# Stick_IMUinator2368.net
KiCad netlist of a schematic drawn in EAGLE
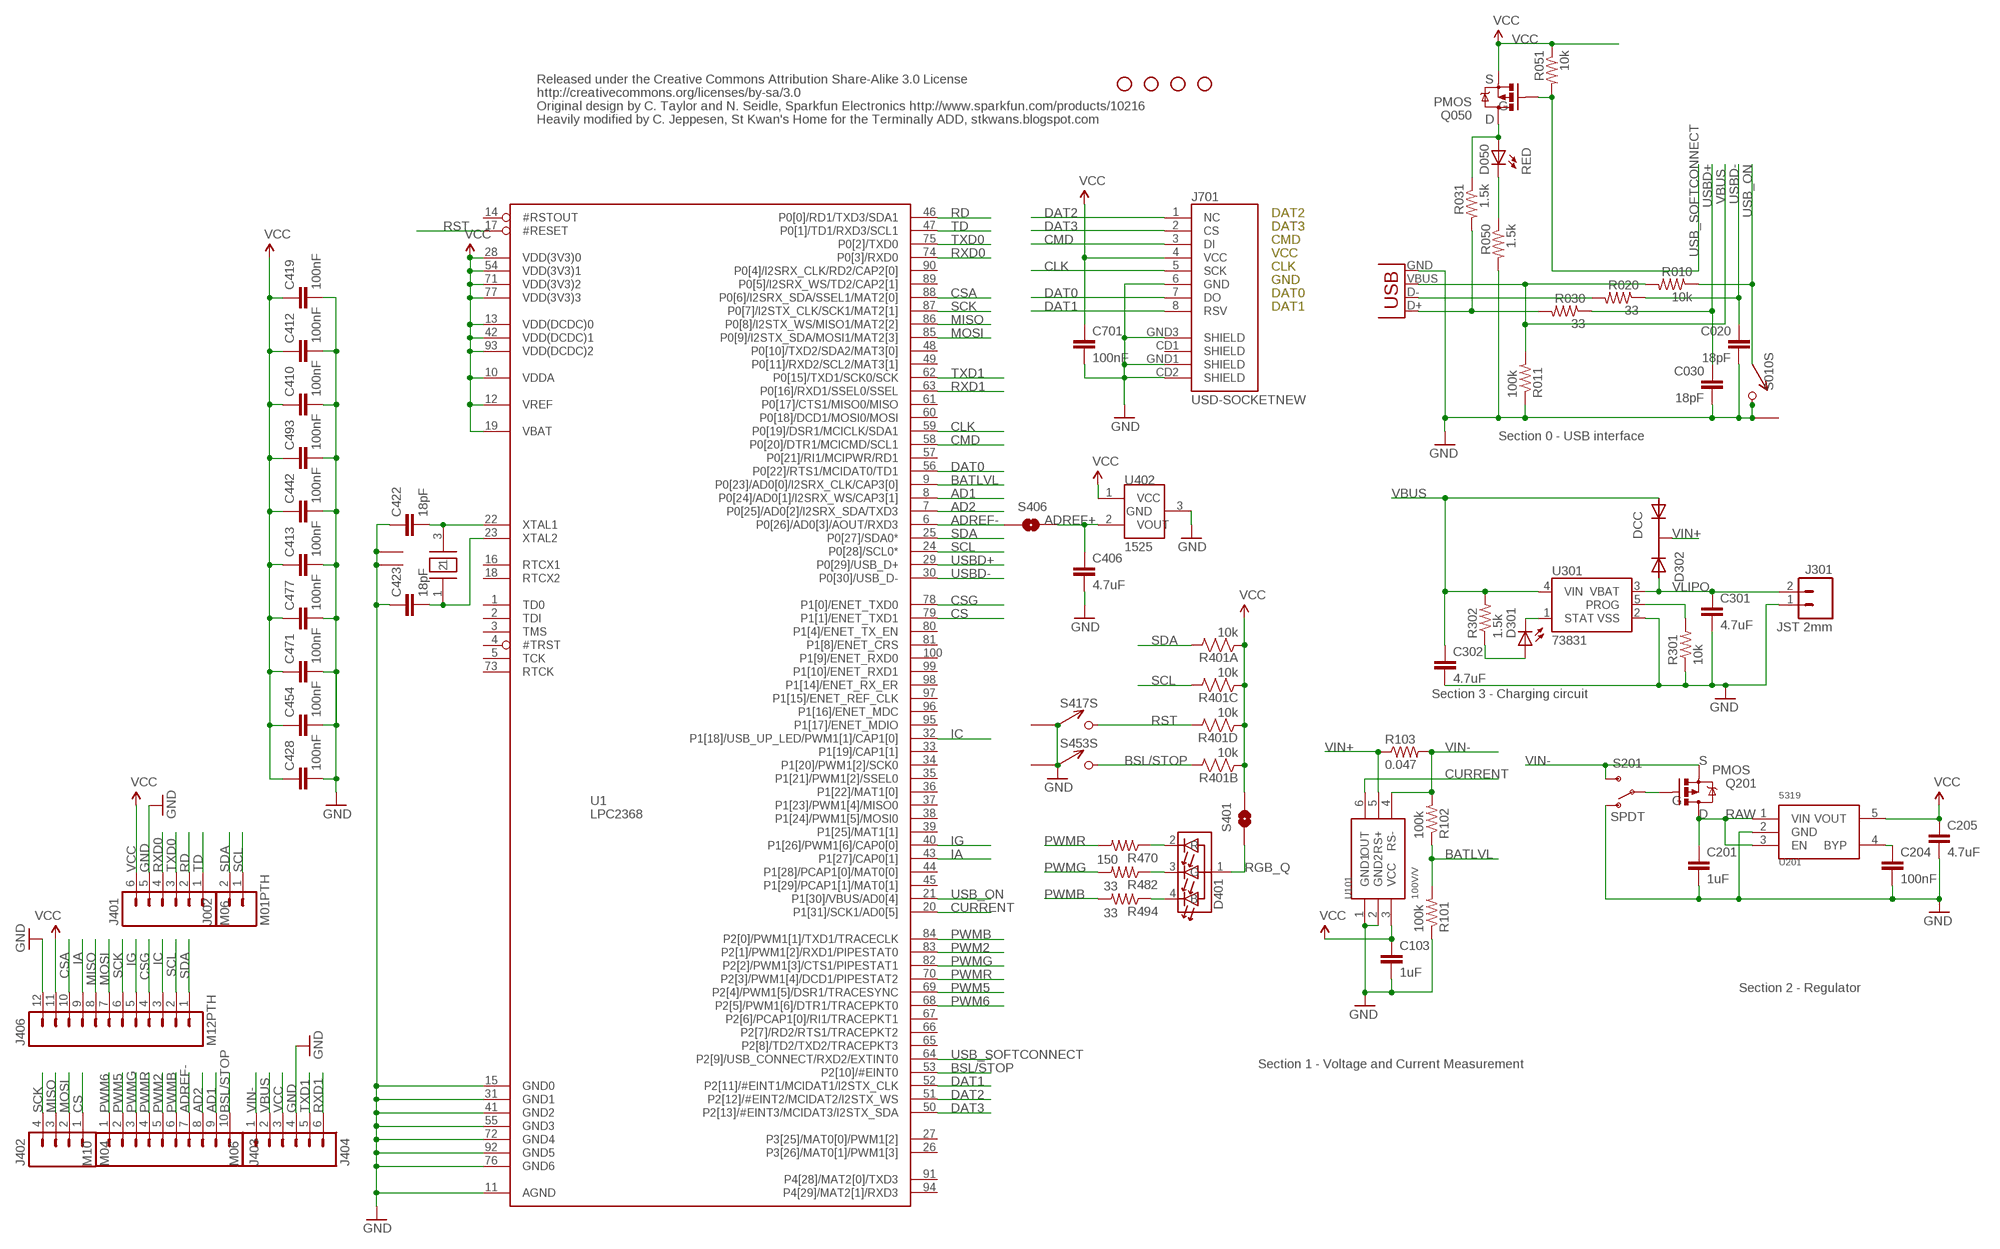
[diagram p0: schematic, sheet 1]

(export (version "E")
  (design (tool "Eeschema 10.0.6"))
  (components
    (comp (ref "C020")
      (value "18pF")
      (footprint "eagle-import:0402-CAP")
      (libsource (lib "eagle-import") (part "CAP0402-CAP"))
    )
    (comp (ref "C030")
      (value "18pF")
      (footprint "eagle-import:0402-CAP")
      (libsource (lib "eagle-import") (part "CAP0402-CAP"))
    )
    (comp (ref "C103")
      (value "1uF")
      (footprint "eagle-import:0402-CAP")
      (libsource (lib "eagle-import") (part "CAP0402-CAP"))
    )
    (comp (ref "C201")
      (value "1uF")
      (footprint "eagle-import:0402-CAP")
      (libsource (lib "eagle-import") (part "CAP0402-CAP"))
    )
    (comp (ref "C204")
      (value "100nF")
      (footprint "eagle-import:0402-CAP")
      (libsource (lib "eagle-import") (part "CAP0402-CAP"))
    )
    (comp (ref "C205")
      (value "4.7uF")
      (footprint "eagle-import:0402-CAP")
      (libsource (lib "eagle-import") (part "CAP0402-CAP"))
    )
    (comp (ref "C301")
      (value "4.7uF")
      (footprint "eagle-import:0402-CAP")
      (libsource (lib "eagle-import") (part "CAP0402-CAP"))
    )
    (comp (ref "C302")
      (value "4.7uF")
      (footprint "eagle-import:0402-CAP")
      (libsource (lib "eagle-import") (part "CAP0402-CAP"))
    )
    (comp (ref "C406")
      (value "4.7uF")
      (footprint "eagle-import:0402-CAP")
      (libsource (lib "eagle-import") (part "CAP0402-CAP"))
    )
    (comp (ref "C410")
      (value "100nF")
      (footprint "eagle-import:0402-CAP")
      (libsource (lib "eagle-import") (part "CAP0402-CAP"))
    )
    (comp (ref "C412")
      (value "100nF")
      (footprint "eagle-import:0402-CAP")
      (libsource (lib "eagle-import") (part "CAP0402-CAP"))
    )
    (comp (ref "C413")
      (value "100nF")
      (footprint "eagle-import:0402-CAP")
      (libsource (lib "eagle-import") (part "CAP0402-CAP"))
    )
    (comp (ref "C419")
      (value "100nF")
      (footprint "eagle-import:0402-CAP")
      (libsource (lib "eagle-import") (part "CAP0402-CAP"))
    )
    (comp (ref "C422")
      (value "18pF")
      (footprint "eagle-import:0402-CAP")
      (libsource (lib "eagle-import") (part "CAP0402-CAP"))
    )
    (comp (ref "C423")
      (value "18pF")
      (footprint "eagle-import:0402-CAP")
      (libsource (lib "eagle-import") (part "CAP0402-CAP"))
    )
    (comp (ref "C428")
      (value "100nF")
      (footprint "eagle-import:0402-CAP")
      (libsource (lib "eagle-import") (part "CAP0402-CAP"))
    )
    (comp (ref "C442")
      (value "100nF")
      (footprint "eagle-import:0402-CAP")
      (libsource (lib "eagle-import") (part "CAP0402-CAP"))
    )
    (comp (ref "C454")
      (value "100nF")
      (footprint "eagle-import:0402-CAP")
      (libsource (lib "eagle-import") (part "CAP0402-CAP"))
    )
    (comp (ref "C471")
      (value "100nF")
      (footprint "eagle-import:0402-CAP")
      (libsource (lib "eagle-import") (part "CAP0402-CAP"))
    )
    (comp (ref "C477")
      (value "100nF")
      (footprint "eagle-import:0402-CAP")
      (libsource (lib "eagle-import") (part "CAP0402-CAP"))
    )
    (comp (ref "C493")
      (value "100nF")
      (footprint "eagle-import:0402-CAP")
      (libsource (lib "eagle-import") (part "CAP0402-CAP"))
    )
    (comp (ref "C701")
      (value "100nF")
      (footprint "eagle-import:0402-CAP")
      (libsource (lib "eagle-import") (part "CAP0402-CAP"))
    )
    (comp (ref "D050")
      (value "RED")
      (footprint "eagle-import:LED-0603")
      (libsource (lib "eagle-import") (part "LED0603"))
    )
    (comp (ref "D301")
      (value "RED")
      (footprint "eagle-import:LED-0603")
      (libsource (lib "eagle-import") (part "LED0603"))
    )
    (comp (ref "D302")
      (value "DCC")
      (footprint "eagle-import:SOT-23-3")
      (libsource (lib "eagle-import") (part "PMEG2005CT"))
    )
    (comp (ref "D401")
      (value "RGB")
      (footprint "eagle-import:HSMF-C118")
      (libsource (lib "eagle-import") (part "HSMF-C118"))
    )
    (comp (ref "J001")
      (value "USBSMD")
      (footprint "eagle-import:USB-MINIB")
      (libsource (lib "eagle-import") (part "USBSMD"))
    )
    (comp (ref "J002")
      (value "M01PTH")
      (footprint "eagle-import:1X02")
      (libsource (lib "eagle-import") (part "M02PTH"))
    )
    (comp (ref "J301")
      (value "JST 2mm")
      (footprint "eagle-import:JST-2-SMD")
      (libsource (lib "eagle-import") (part "M02-JST-2MM-SMT"))
    )
    (comp (ref "J401")
      (value "M06")
      (footprint "eagle-import:1X06")
      (libsource (lib "eagle-import") (part "M06SIP"))
    )
    (comp (ref "J402")
      (value "M04")
      (footprint "eagle-import:1X04")
      (libsource (lib "eagle-import") (part "M04PTH"))
    )
    (comp (ref "J403")
      (value "M10")
      (footprint "eagle-import:1X10")
      (libsource (lib "eagle-import") (part "M10{dblquote}"))
    )
    (comp (ref "J404")
      (value "M06")
      (footprint "eagle-import:1X06")
      (libsource (lib "eagle-import") (part "M06SIP"))
    )
    (comp (ref "J406")
      (value "M12PTH")
      (footprint "eagle-import:1X12")
      (libsource (lib "eagle-import") (part "M12PTH"))
    )
    (comp (ref "J701")
      (value "USD-SOCKETNEW")
      (footprint "eagle-import:MICRO-SD-SOCKET-PP")
      (libsource (lib "eagle-import") (part "USD-SOCKETNEW"))
    )
    (comp (ref "JP1")
      (value "STAND-OFF")
      (footprint "eagle-import:STAND-OFF")
      (libsource (lib "eagle-import") (part "STAND-OFF"))
    )
    (comp (ref "JP2")
      (value "STAND-OFF")
      (footprint "eagle-import:STAND-OFF")
      (libsource (lib "eagle-import") (part "STAND-OFF"))
    )
    (comp (ref "JP3")
      (value "STAND-OFF")
      (footprint "eagle-import:STAND-OFF")
      (libsource (lib "eagle-import") (part "STAND-OFF"))
    )
    (comp (ref "JP4")
      (value "STAND-OFF")
      (footprint "eagle-import:STAND-OFF")
      (libsource (lib "eagle-import") (part "STAND-OFF"))
    )
    (comp (ref "Q050")
      (value "PMOS")
      (footprint "eagle-import:SOT23-3")
      (libsource (lib "eagle-import") (part "MOSFET-PCHANNELSMD"))
    )
    (comp (ref "Q201")
      (value "PMOS")
      (footprint "eagle-import:SOT23-3")
      (libsource (lib "eagle-import") (part "MOSFET-PCHANNELSMD"))
    )
    (comp (ref "R010")
      (value "10k")
      (footprint "eagle-import:0402-RES")
      (libsource (lib "eagle-import") (part "RESISTOR0402-RES"))
    )
    (comp (ref "R011")
      (value "100k")
      (footprint "eagle-import:0402-RES")
      (libsource (lib "eagle-import") (part "RESISTOR0402-RES"))
    )
    (comp (ref "R020")
      (value "33")
      (footprint "eagle-import:0402-RES")
      (libsource (lib "eagle-import") (part "RESISTOR0402-RES"))
    )
    (comp (ref "R030")
      (value "33")
      (footprint "eagle-import:0402-RES")
      (libsource (lib "eagle-import") (part "RESISTOR0402-RES"))
    )
    (comp (ref "R031")
      (value "1.5k")
      (footprint "eagle-import:0402-RES")
      (libsource (lib "eagle-import") (part "RESISTOR0402-RES"))
    )
    (comp (ref "R050")
      (value "1.5k")
      (footprint "eagle-import:0402-RES")
      (libsource (lib "eagle-import") (part "RESISTOR0402-RES"))
    )
    (comp (ref "R051")
      (value "10k")
      (footprint "eagle-import:0402-RES")
      (libsource (lib "eagle-import") (part "RESISTOR0402-RES"))
    )
    (comp (ref "R101")
      (value "100k")
      (footprint "eagle-import:0402-RES")
      (libsource (lib "eagle-import") (part "RESISTOR0402-RES"))
    )
    (comp (ref "R102")
      (value "100k")
      (footprint "eagle-import:0402-RES")
      (libsource (lib "eagle-import") (part "RESISTOR0402-RES"))
    )
    (comp (ref "R103")
      (value "0.047")
      (footprint "eagle-import:0402-RES")
      (libsource (lib "eagle-import") (part "RESISTOR0402-RES"))
    )
    (comp (ref "R301")
      (value "10k")
      (footprint "eagle-import:0402-RES")
      (libsource (lib "eagle-import") (part "RESISTOR0402-RES"))
    )
    (comp (ref "R302")
      (value "1.5k")
      (footprint "eagle-import:0402-RES")
      (libsource (lib "eagle-import") (part "RESISTOR0402-RES"))
    )
    (comp (ref "R401")
      (value "10k")
      (footprint "eagle-import:CRA04")
      (libsource (lib "eagle-import") (part "RP404"))
    )
    (comp (ref "R470")
      (value "150")
      (footprint "eagle-import:0402-RES")
      (libsource (lib "eagle-import") (part "RESISTOR0402-RES"))
    )
    (comp (ref "R482")
      (value "33")
      (footprint "eagle-import:0402-RES")
      (libsource (lib "eagle-import") (part "RESISTOR0402-RES"))
    )
    (comp (ref "R494")
      (value "33")
      (footprint "eagle-import:0402-RES")
      (libsource (lib "eagle-import") (part "RESISTOR0402-RES"))
    )
    (comp (ref "S010")
      (value "SPST")
      (footprint "eagle-import:B3U-1100P")
      (libsource (lib "eagle-import") (part "B3U-1100P"))
    )
    (comp (ref "S201")
      (value "SPDT")
      (footprint "eagle-import:AYZ0202")
      (libsource (lib "eagle-import") (part "SWITCH-SPSTSMD"))
    )
    (comp (ref "S401")
      (value "SOLDERJUMPERNO")
      (footprint "eagle-import:SJ_2S-NO")
      (libsource (lib "eagle-import") (part "SOLDERJUMPERNO"))
    )
    (comp (ref "S406")
      (value "SOLDERJUMPERNO")
      (footprint "eagle-import:SJ_2S-NO")
      (libsource (lib "eagle-import") (part "SOLDERJUMPERNO"))
    )
    (comp (ref "S417")
      (value "SPST")
      (footprint "eagle-import:B3U-1100P")
      (libsource (lib "eagle-import") (part "B3U-1100P"))
    )
    (comp (ref "S453")
      (value "SPST")
      (footprint "eagle-import:B3U-1100P")
      (libsource (lib "eagle-import") (part "B3U-1100P"))
    )
    (comp (ref "U1")
      (value "LPC2368")
      (footprint "eagle-import:LQFP100")
      (libsource (lib "eagle-import") (part "LPC2368"))
    )
    (comp (ref "U101")
      (value "100V/V")
      (footprint "eagle-import:SOT-23-6")
      (libsource (lib "eagle-import") (part "MAX4173"))
    )
    (comp (ref "U201")
      (value "5319")
      (footprint "eagle-import:SOT-23-5")
      (libsource (lib "eagle-import") (part "MIC5319D5"))
    )
    (comp (ref "U301")
      (value "73831")
      (footprint "eagle-import:SOT23-5")
      (libsource (lib "eagle-import") (part "MCP73831"))
    )
    (comp (ref "U402")
      (value "1525")
      (footprint "eagle-import:SOT-23-3")
      (libsource (lib "eagle-import") (part "MCP1525"))
    )
    (comp (ref "Y401")
      (value "12M")
      (footprint "eagle-import:CRYSTAL_SMD")
      (libsource (lib "eagle-import") (part "TSX-3225"))
    )
  )
  (nets
    (net (code "1") (name "/AD1") (class "Default")
      (node (ref "J403") (pin "9") (pinfunction "9_9") (pintype "passive"))
      (node (ref "U1") (pin "8") (pinfunction "P0[24]/AD0[1]/I2SRX_WS/CAP3[1]_8") (pintype "bidirectional"))
    )
    (net (code "2") (name "/AD2") (class "Default")
      (node (ref "J403") (pin "8") (pinfunction "8_8") (pintype "passive"))
      (node (ref "U1") (pin "7") (pinfunction "P0[25]/AD0[2]/I2SRX_SDA/TXD3_7") (pintype "bidirectional"))
    )
    (net (code "3") (name "/ADREF+") (class "Default")
      (node (ref "C406") (pin "1") (pinfunction "1_1") (pintype "passive"))
      (node (ref "S406") (pin "1") (pinfunction "1_1") (pintype "passive"))
      (node (ref "U402") (pin "2") (pinfunction "VOUT_2") (pintype "bidirectional"))
    )
    (net (code "4") (name "/ADREF-") (class "Default")
      (node (ref "J403") (pin "7") (pinfunction "7_7") (pintype "passive"))
      (node (ref "S406") (pin "2") (pinfunction "2_2") (pintype "passive"))
      (node (ref "U1") (pin "6") (pinfunction "P0[26]/AD0[3]/AOUT/RXD3_6") (pintype "bidirectional"))
    )
    (net (code "5") (name "/BATLVL") (class "Default")
      (node (ref "R101") (pin "2") (pinfunction "2_2") (pintype "passive"))
      (node (ref "R102") (pin "1") (pinfunction "1_1") (pintype "passive"))
      (node (ref "U1") (pin "9") (pinfunction "P0[23]/AD0[0]/I2SRX_CLK/CAP3[0]_9") (pintype "bidirectional"))
    )
    (net (code "6") (name "/BSL{slash}STOP") (class "Default")
      (node (ref "J403") (pin "10") (pinfunction "10_10") (pintype "passive"))
      (node (ref "R401") (pin "7") (pinfunction "2_7") (pintype "passive"))
      (node (ref "S453") (pin "P$2") (pinfunction "2_P$2") (pintype "bidirectional"))
      (node (ref "U1") (pin "53") (pinfunction "P2[10]/#EINT0_53") (pintype "bidirectional"))
    )
    (net (code "7") (name "/CLK") (class "Default")
      (node (ref "J701") (pin "5") (pinfunction "SCK_5") (pintype "bidirectional"))
      (node (ref "U1") (pin "59") (pinfunction "P0[19]/DSR1/MCICLK/SDA1_59") (pintype "bidirectional"))
    )
    (net (code "8") (name "/CMD") (class "Default")
      (node (ref "J701") (pin "3") (pinfunction "DI_3") (pintype "bidirectional"))
      (node (ref "U1") (pin "58") (pinfunction "P0[20]/DTR1/MCICMD/SCL1_58") (pintype "bidirectional"))
    )
    (net (code "9") (name "/CS") (class "Default")
      (node (ref "J402") (pin "1") (pinfunction "1_1") (pintype "passive"))
      (node (ref "U1") (pin "79") (pinfunction "P1[1]/ENET_TXD1_79") (pintype "bidirectional"))
    )
    (net (code "10") (name "/CSA") (class "Default")
      (node (ref "J406") (pin "10") (pinfunction "10_10") (pintype "passive"))
      (node (ref "U1") (pin "88") (pinfunction "P0[6]/I2SRX_SDA/SSEL1/MAT2[0]_88") (pintype "bidirectional"))
    )
    (net (code "11") (name "/CSG") (class "Default")
      (node (ref "J406") (pin "4") (pinfunction "4_4") (pintype "passive"))
      (node (ref "U1") (pin "78") (pinfunction "P1[0]/ENET_TXD0_78") (pintype "bidirectional"))
    )
    (net (code "12") (name "/CURRENT") (class "Default")
      (node (ref "U1") (pin "20") (pinfunction "P1[31]/SCK1/AD0[5]_20") (pintype "bidirectional"))
      (node (ref "U101") (pin "6") (pinfunction "OUT_6") (pintype "bidirectional"))
    )
    (net (code "13") (name "/DAT0") (class "Default")
      (node (ref "J701") (pin "7") (pinfunction "DO_7") (pintype "bidirectional"))
      (node (ref "U1") (pin "56") (pinfunction "P0[22]/RTS1/MCIDAT0/TD1_56") (pintype "bidirectional"))
    )
    (net (code "14") (name "/DAT1") (class "Default")
      (node (ref "J701") (pin "8") (pinfunction "RSV_8") (pintype "bidirectional"))
      (node (ref "U1") (pin "52") (pinfunction "P2[11]/#EINT1/MCIDAT1/I2STX_CLK_52") (pintype "bidirectional"))
    )
    (net (code "15") (name "/DAT2") (class "Default")
      (node (ref "J701") (pin "1") (pinfunction "NC_1") (pintype "bidirectional"))
      (node (ref "U1") (pin "51") (pinfunction "P2[12]/#EINT2/MCIDAT2/I2STX_WS_51") (pintype "bidirectional"))
    )
    (net (code "16") (name "/DAT3") (class "Default")
      (node (ref "J701") (pin "2") (pinfunction "CS_2") (pintype "bidirectional"))
      (node (ref "U1") (pin "50") (pinfunction "P2[13]/#EINT3/MCIDAT3/I2STX_SDA_50") (pintype "bidirectional"))
    )
    (net (code "17") (name "/IA") (class "Default")
      (node (ref "J406") (pin "9") (pinfunction "9_9") (pintype "passive"))
      (node (ref "U1") (pin "43") (pinfunction "P1[27]/CAP0[1]_43") (pintype "bidirectional"))
    )
    (net (code "18") (name "/IC") (class "Default")
      (node (ref "J406") (pin "3") (pinfunction "3_3") (pintype "passive"))
      (node (ref "U1") (pin "32") (pinfunction "P1[18]/USB_UP_LED/PWM1[1]/CAP1[0]_32") (pintype "bidirectional"))
    )
    (net (code "19") (name "/IG") (class "Default")
      (node (ref "J406") (pin "5") (pinfunction "5_5") (pintype "passive"))
      (node (ref "U1") (pin "40") (pinfunction "P1[26]/PWM1[6]/CAP0[0]_40") (pintype "bidirectional"))
    )
    (net (code "20") (name "/MISO") (class "Default")
      (node (ref "J402") (pin "3") (pinfunction "3_3") (pintype "passive"))
      (node (ref "J406") (pin "8") (pinfunction "8_8") (pintype "passive"))
      (node (ref "U1") (pin "86") (pinfunction "P0[8]/I2STX_WS/MISO1/MAT2[2]_86") (pintype "bidirectional"))
    )
    (net (code "21") (name "/MOSI") (class "Default")
      (node (ref "J402") (pin "2") (pinfunction "2_2") (pintype "passive"))
      (node (ref "J406") (pin "7") (pinfunction "7_7") (pintype "passive"))
      (node (ref "U1") (pin "85") (pinfunction "P0[9]/I2STX_SDA/MOSI1/MAT2[3]_85") (pintype "bidirectional"))
    )
    (net (code "22") (name "/PWM2") (class "Default")
      (node (ref "J403") (pin "5") (pinfunction "5_5") (pintype "passive"))
      (node (ref "U1") (pin "83") (pinfunction "P2[1]/PWM1[2]/RXD1/PIPESTAT0_83") (pintype "bidirectional"))
    )
    (net (code "23") (name "/PWM5") (class "Default")
      (node (ref "J403") (pin "2") (pinfunction "2_2") (pintype "passive"))
      (node (ref "U1") (pin "69") (pinfunction "P2[4]/PWM1[5]/DSR1/TRACESYNC_69") (pintype "bidirectional"))
    )
    (net (code "24") (name "/PWM6") (class "Default")
      (node (ref "J403") (pin "1") (pinfunction "1_1") (pintype "passive"))
      (node (ref "U1") (pin "68") (pinfunction "P2[5]/PWM1[6]/DTR1/TRACEPKT0_68") (pintype "bidirectional"))
    )
    (net (code "25") (name "/PWMB") (class "Default")
      (node (ref "J403") (pin "6") (pinfunction "6_6") (pintype "passive"))
      (node (ref "R494") (pin "2") (pinfunction "2_2") (pintype "passive"))
      (node (ref "U1") (pin "84") (pinfunction "P2[0]/PWM1[1]/TXD1/TRACECLK_84") (pintype "bidirectional"))
    )
    (net (code "26") (name "/PWMG") (class "Default")
      (node (ref "J403") (pin "3") (pinfunction "3_3") (pintype "passive"))
      (node (ref "R482") (pin "2") (pinfunction "2_2") (pintype "passive"))
      (node (ref "U1") (pin "82") (pinfunction "P2[2]/PWM1[3]/CTS1/PIPESTAT1_82") (pintype "bidirectional"))
    )
    (net (code "27") (name "/PWMR") (class "Default")
      (node (ref "J403") (pin "4") (pinfunction "4_4") (pintype "passive"))
      (node (ref "R470") (pin "2") (pinfunction "2_2") (pintype "passive"))
      (node (ref "U1") (pin "70") (pinfunction "P2[3]/PWM1[4]/DCD1/PIPESTAT2_70") (pintype "bidirectional"))
    )
    (net (code "28") (name "/RAW") (class "Default")
      (node (ref "C201") (pin "1") (pinfunction "1_1") (pintype "passive"))
      (node (ref "Q201") (pin "3") (pinfunction "D_3") (pintype "passive"))
      (node (ref "U201") (pin "1") (pinfunction "VIN_1") (pintype "bidirectional"))
      (node (ref "U201") (pin "3") (pinfunction "EN_3") (pintype "bidirectional"))
    )
    (net (code "29") (name "/RD") (class "Default")
      (node (ref "J401") (pin "2") (pinfunction "2_2") (pintype "passive"))
      (node (ref "U1") (pin "46") (pinfunction "P0[0]/RD1/TXD3/SDA1_46") (pintype "bidirectional"))
    )
    (net (code "30") (name "/RGB_Q") (class "Default")
      (node (ref "D401") (pin "1") (pinfunction "A_1") (pintype "passive"))
      (node (ref "S401") (pin "1") (pinfunction "1_1") (pintype "passive"))
    )
    (net (code "31") (name "/RST") (class "Default")
      (node (ref "R401") (pin "5") (pinfunction "2_5") (pintype "passive"))
      (node (ref "S417") (pin "P$2") (pinfunction "2_P$2") (pintype "bidirectional"))
      (node (ref "U1") (pin "17") (pinfunction "#RESET_17") (pintype "bidirectional"))
    )
    (net (code "32") (name "/RXD0") (class "Default")
      (node (ref "J401") (pin "4") (pinfunction "4_4") (pintype "passive"))
      (node (ref "U1") (pin "74") (pinfunction "P0[3]/RXD0_74") (pintype "bidirectional"))
    )
    (net (code "33") (name "/RXD1") (class "Default")
      (node (ref "J404") (pin "6") (pinfunction "6_6") (pintype "passive"))
      (node (ref "U1") (pin "63") (pinfunction "P0[16]/RXD1/SSEL0/SSEL_63") (pintype "bidirectional"))
    )
    (net (code "34") (name "/SCK") (class "Default")
      (node (ref "J402") (pin "4") (pinfunction "4_4") (pintype "passive"))
      (node (ref "J406") (pin "6") (pinfunction "6_6") (pintype "passive"))
      (node (ref "U1") (pin "87") (pinfunction "P0[7]/I2STX_CLK/SCK1/MAT2[1]_87") (pintype "bidirectional"))
    )
    (net (code "35") (name "/SCL") (class "Default")
      (node (ref "J002") (pin "1") (pinfunction "1_1") (pintype "passive"))
      (node (ref "J406") (pin "2") (pinfunction "2_2") (pintype "passive"))
      (node (ref "R401") (pin "6") (pinfunction "2_6") (pintype "passive"))
      (node (ref "U1") (pin "24") (pinfunction "P0[28]/SCL0*_24") (pintype "bidirectional"))
    )
    (net (code "36") (name "/SDA") (class "Default")
      (node (ref "J002") (pin "2") (pinfunction "2_2") (pintype "passive"))
      (node (ref "J406") (pin "1") (pinfunction "1_1") (pintype "passive"))
      (node (ref "R401") (pin "8") (pinfunction "2_8") (pintype "passive"))
      (node (ref "U1") (pin "25") (pinfunction "P0[27]/SDA0*_25") (pintype "bidirectional"))
    )
    (net (code "37") (name "/TD") (class "Default")
      (node (ref "J401") (pin "1") (pinfunction "1_1") (pintype "passive"))
      (node (ref "U1") (pin "47") (pinfunction "P0[1]/TD1/RXD3/SCL1_47") (pintype "bidirectional"))
    )
    (net (code "38") (name "/TXD0") (class "Default")
      (node (ref "J401") (pin "3") (pinfunction "3_3") (pintype "passive"))
      (node (ref "U1") (pin "75") (pinfunction "P0[2]/TXD0_75") (pintype "bidirectional"))
    )
    (net (code "39") (name "/TXD1") (class "Default")
      (node (ref "J404") (pin "5") (pinfunction "5_5") (pintype "passive"))
      (node (ref "U1") (pin "62") (pinfunction "P0[15]/TXD1/SCK0/SCK_62") (pintype "bidirectional"))
    )
    (net (code "40") (name "/USBD+") (class "Default")
      (node (ref "C030") (pin "1") (pinfunction "1_1") (pintype "passive"))
      (node (ref "R030") (pin "1") (pinfunction "1_1") (pintype "passive"))
      (node (ref "U1") (pin "29") (pinfunction "P0[29]/USB_D+_29") (pintype "bidirectional"))
    )
    (net (code "41") (name "/USBD-") (class "Default")
      (node (ref "C020") (pin "1") (pinfunction "1_1") (pintype "passive"))
      (node (ref "R020") (pin "1") (pinfunction "1_1") (pintype "passive"))
      (node (ref "U1") (pin "30") (pinfunction "P0[30]/USB_D-_30") (pintype "bidirectional"))
    )
    (net (code "42") (name "/USB_ON") (class "Default")
      (node (ref "R010") (pin "1") (pinfunction "1_1") (pintype "passive"))
      (node (ref "S010") (pin "P$1") (pinfunction "1_P$1") (pintype "bidirectional"))
      (node (ref "U1") (pin "21") (pinfunction "P1[30]/VBUS/AD0[4]_21") (pintype "bidirectional"))
    )
    (net (code "43") (name "/USB_SOFTCONNECT") (class "Default")
      (node (ref "Q050") (pin "1") (pinfunction "G_1") (pintype "passive"))
      (node (ref "R051") (pin "2") (pinfunction "2_2") (pintype "passive"))
      (node (ref "U1") (pin "64") (pinfunction "P2[9]/USB_CONNECT/RXD2/EXTINT0_64") (pintype "bidirectional"))
    )
    (net (code "44") (name "/VBUS") (class "Default")
      (node (ref "C302") (pin "1") (pinfunction "1_1") (pintype "passive"))
      (node (ref "D302") (pin "1") (pinfunction "A1_1") (pintype "passive"))
      (node (ref "J001") (pin "VBUS") (pinfunction "VBUS_VBUS") (pintype "bidirectional"))
      (node (ref "J404") (pin "2") (pinfunction "2_2") (pintype "passive"))
      (node (ref "R010") (pin "2") (pinfunction "2_2") (pintype "passive"))
      (node (ref "R011") (pin "2") (pinfunction "2_2") (pintype "passive"))
      (node (ref "R302") (pin "2") (pinfunction "2_2") (pintype "passive"))
      (node (ref "U301") (pin "4") (pinfunction "VIN_4") (pintype "power_in"))
    )
    (net (code "45") (name "/VIN+") (class "Default")
      (node (ref "D302") (pin "3") (pinfunction "K_3") (pintype "passive"))
      (node (ref "R103") (pin "1") (pinfunction "1_1") (pintype "passive"))
      (node (ref "U101") (pin "5") (pinfunction "RS+_5") (pintype "bidirectional"))
    )
    (net (code "46") (name "/VIN-") (class "Default")
      (node (ref "J404") (pin "1") (pinfunction "1_1") (pintype "passive"))
      (node (ref "Q201") (pin "2") (pinfunction "S_2") (pintype "passive"))
      (node (ref "R102") (pin "2") (pinfunction "2_2") (pintype "passive"))
      (node (ref "R103") (pin "2") (pinfunction "2_2") (pintype "passive"))
      (node (ref "S201") (pin "3") (pinfunction "S_3") (pintype "passive"))
      (node (ref "U101") (pin "4") (pinfunction "RS-_4") (pintype "bidirectional"))
    )
    (net (code "47") (name "/VLIPO") (class "Default")
      (node (ref "C301") (pin "1") (pinfunction "1_1") (pintype "passive"))
      (node (ref "D302") (pin "2") (pinfunction "A2_2") (pintype "passive"))
      (node (ref "J301") (pin "2") (pinfunction "2_2") (pintype "passive"))
      (node (ref "U301") (pin "3") (pinfunction "VBAT_3") (pintype "power_in"))
    )
    (net (code "48") (name "GND") (class "Default")
      (node (ref "C020") (pin "2") (pinfunction "2_2") (pintype "passive"))
      (node (ref "C030") (pin "2") (pinfunction "2_2") (pintype "passive"))
      (node (ref "C103") (pin "2") (pinfunction "2_2") (pintype "passive"))
      (node (ref "C201") (pin "2") (pinfunction "2_2") (pintype "passive"))
      (node (ref "C204") (pin "2") (pinfunction "2_2") (pintype "passive"))
      (node (ref "C205") (pin "2") (pinfunction "2_2") (pintype "passive"))
      (node (ref "C301") (pin "2") (pinfunction "2_2") (pintype "passive"))
      (node (ref "C302") (pin "2") (pinfunction "2_2") (pintype "passive"))
      (node (ref "C406") (pin "2") (pinfunction "2_2") (pintype "passive"))
      (node (ref "C410") (pin "2") (pinfunction "2_2") (pintype "passive"))
      (node (ref "C412") (pin "2") (pinfunction "2_2") (pintype "passive"))
      (node (ref "C413") (pin "2") (pinfunction "2_2") (pintype "passive"))
      (node (ref "C419") (pin "2") (pinfunction "2_2") (pintype "passive"))
      (node (ref "C422") (pin "1") (pinfunction "1_1") (pintype "passive"))
      (node (ref "C423") (pin "1") (pinfunction "1_1") (pintype "passive"))
      (node (ref "C428") (pin "2") (pinfunction "2_2") (pintype "passive"))
      (node (ref "C442") (pin "2") (pinfunction "2_2") (pintype "passive"))
      (node (ref "C454") (pin "2") (pinfunction "2_2") (pintype "passive"))
      (node (ref "C471") (pin "2") (pinfunction "2_2") (pintype "passive"))
      (node (ref "C477") (pin "2") (pinfunction "2_2") (pintype "passive"))
      (node (ref "C493") (pin "2") (pinfunction "2_2") (pintype "passive"))
      (node (ref "C701") (pin "2") (pinfunction "2_2") (pintype "passive"))
      (node (ref "J001") (pin "GND") (pinfunction "GND_GND") (pintype "bidirectional"))
      (node (ref "J301") (pin "1") (pinfunction "1_1") (pintype "passive"))
      (node (ref "J401") (pin "5") (pinfunction "5_5") (pintype "passive"))
      (node (ref "J404") (pin "4") (pinfunction "4_4") (pintype "passive"))
      (node (ref "J406") (pin "12") (pinfunction "12_12") (pintype "passive"))
      (node (ref "J701") (pin "6") (pinfunction "GND_6") (pintype "bidirectional"))
      (node (ref "J701") (pin "CD2") (pinfunction "SHIELD_CD2") (pintype "bidirectional"))
      (node (ref "J701") (pin "GND1") (pinfunction "SHIELD_GND1") (pintype "bidirectional"))
      (node (ref "J701") (pin "GND3") (pinfunction "SHIELD_GND3") (pintype "bidirectional"))
      (node (ref "R011") (pin "1") (pinfunction "1_1") (pintype "passive"))
      (node (ref "R050") (pin "2") (pinfunction "2_2") (pintype "passive"))
      (node (ref "R101") (pin "1") (pinfunction "1_1") (pintype "passive"))
      (node (ref "R301") (pin "1") (pinfunction "1_1") (pintype "passive"))
      (node (ref "S010") (pin "P$2") (pinfunction "2_P$2") (pintype "bidirectional"))
      (node (ref "S010") (pin "P$3") (pinfunction "1_P$3") (pintype "bidirectional"))
      (node (ref "S201") (pin "1") (pinfunction "O_1") (pintype "passive"))
      (node (ref "S417") (pin "P$1") (pinfunction "1_P$1") (pintype "bidirectional"))
      (node (ref "S417") (pin "P$3") (pinfunction "1_P$3") (pintype "bidirectional"))
      (node (ref "S453") (pin "P$1") (pinfunction "1_P$1") (pintype "bidirectional"))
      (node (ref "S453") (pin "P$3") (pinfunction "1_P$3") (pintype "bidirectional"))
      (node (ref "U1") (pin "11") (pinfunction "AGND_11") (pintype "bidirectional"))
      (node (ref "U1") (pin "15") (pinfunction "GND0_15") (pintype "bidirectional"))
      (node (ref "U1") (pin "31") (pinfunction "GND1_31") (pintype "bidirectional"))
      (node (ref "U1") (pin "41") (pinfunction "GND2_41") (pintype "bidirectional"))
      (node (ref "U1") (pin "55") (pinfunction "GND3_55") (pintype "bidirectional"))
      (node (ref "U1") (pin "72") (pinfunction "GND4_72") (pintype "bidirectional"))
      (node (ref "U1") (pin "76") (pinfunction "GND6_76") (pintype "bidirectional"))
      (node (ref "U1") (pin "92") (pinfunction "GND5_92") (pintype "bidirectional"))
      (node (ref "U101") (pin "1") (pinfunction "GND1_1") (pintype "bidirectional"))
      (node (ref "U101") (pin "2") (pinfunction "GND2_2") (pintype "bidirectional"))
      (node (ref "U201") (pin "2") (pinfunction "GND_2") (pintype "bidirectional"))
      (node (ref "U301") (pin "2") (pinfunction "VSS_2") (pintype "power_in"))
      (node (ref "U402") (pin "3") (pinfunction "GND_3") (pintype "bidirectional"))
      (node (ref "Y401") (pin "2") (pinfunction "1_2") (pintype "bidirectional"))
      (node (ref "Y401") (pin "4") (pinfunction "1_4") (pintype "bidirectional"))
    )
    (net (code "49") (name "Net-(D050-PadC)") (class "Default")
      (node (ref "D050") (pin "C") (pinfunction "C_C") (pintype "passive"))
      (node (ref "R050") (pin "1") (pinfunction "1_1") (pintype "passive"))
    )
    (net (code "50") (name "Net-(D301-PadA)") (class "Default")
      (node (ref "D301") (pin "A") (pinfunction "A_A") (pintype "passive"))
      (node (ref "R302") (pin "1") (pinfunction "1_1") (pintype "passive"))
    )
    (net (code "51") (name "Net-(D401-B)") (class "Default")
      (node (ref "D401") (pin "4") (pinfunction "B_4") (pintype "passive"))
      (node (ref "R494") (pin "1") (pinfunction "1_1") (pintype "passive"))
    )
    (net (code "52") (name "Net-(D401-G)") (class "Default")
      (node (ref "D401") (pin "3") (pinfunction "G_3") (pintype "passive"))
      (node (ref "R482") (pin "1") (pinfunction "1_1") (pintype "passive"))
    )
    (net (code "53") (name "Net-(D401-R)") (class "Default")
      (node (ref "D401") (pin "2") (pinfunction "R_2") (pintype "passive"))
      (node (ref "R470") (pin "1") (pinfunction "1_1") (pintype "passive"))
    )
    (net (code "54") (name "Net-(J001-PadD+)") (class "Default")
      (node (ref "J001") (pin "D+") (pinfunction "D+_D+") (pintype "bidirectional"))
      (node (ref "R030") (pin "2") (pinfunction "2_2") (pintype "passive"))
      (node (ref "R031") (pin "2") (pinfunction "2_2") (pintype "passive"))
    )
    (net (code "55") (name "Net-(J001-PadD-)") (class "Default")
      (node (ref "J001") (pin "D-") (pinfunction "D-_D-") (pintype "bidirectional"))
      (node (ref "R020") (pin "2") (pinfunction "2_2") (pintype "passive"))
    )
    (net (code "56") (name "Net-(Q050-D)") (class "Default")
      (node (ref "D050") (pin "A") (pinfunction "A_A") (pintype "passive"))
      (node (ref "Q050") (pin "3") (pinfunction "D_3") (pintype "passive"))
      (node (ref "R031") (pin "1") (pinfunction "1_1") (pintype "passive"))
    )
    (net (code "57") (name "Net-(Q201-G)") (class "Default")
      (node (ref "Q201") (pin "1") (pinfunction "G_1") (pintype "passive"))
      (node (ref "S201") (pin "2") (pinfunction "P_2") (pintype "passive"))
    )
    (net (code "58") (name "Net-(U1-XTAL1)") (class "Default")
      (node (ref "C422") (pin "2") (pinfunction "2_2") (pintype "passive"))
      (node (ref "U1") (pin "22") (pinfunction "XTAL1_22") (pintype "bidirectional"))
      (node (ref "Y401") (pin "3") (pinfunction "2_3") (pintype "bidirectional"))
    )
    (net (code "59") (name "Net-(U1-XTAL2)") (class "Default")
      (node (ref "C423") (pin "2") (pinfunction "2_2") (pintype "passive"))
      (node (ref "U1") (pin "23") (pinfunction "XTAL2_23") (pintype "bidirectional"))
      (node (ref "Y401") (pin "1") (pinfunction "1_1") (pintype "bidirectional"))
    )
    (net (code "60") (name "Net-(U201-BYP)") (class "Default")
      (node (ref "C204") (pin "1") (pinfunction "1_1") (pintype "passive"))
      (node (ref "U201") (pin "4") (pinfunction "BYP_4") (pintype "bidirectional"))
    )
    (net (code "61") (name "Net-(U301-PROG)") (class "Default")
      (node (ref "R301") (pin "2") (pinfunction "2_2") (pintype "passive"))
      (node (ref "U301") (pin "5") (pinfunction "PROG_5") (pintype "input"))
    )
    (net (code "62") (name "Net-(U301-STAT)") (class "Default")
      (node (ref "D301") (pin "C") (pinfunction "C_C") (pintype "passive"))
      (node (ref "U301") (pin "1") (pinfunction "STAT_1") (pintype "output"))
    )
    (net (code "63") (name "VCC") (class "Default")
      (node (ref "C103") (pin "1") (pinfunction "1_1") (pintype "passive"))
      (node (ref "C205") (pin "1") (pinfunction "1_1") (pintype "passive"))
      (node (ref "C410") (pin "1") (pinfunction "1_1") (pintype "passive"))
      (node (ref "C412") (pin "1") (pinfunction "1_1") (pintype "passive"))
      (node (ref "C413") (pin "1") (pinfunction "1_1") (pintype "passive"))
      (node (ref "C419") (pin "1") (pinfunction "1_1") (pintype "passive"))
      (node (ref "C428") (pin "1") (pinfunction "1_1") (pintype "passive"))
      (node (ref "C442") (pin "1") (pinfunction "1_1") (pintype "passive"))
      (node (ref "C454") (pin "1") (pinfunction "1_1") (pintype "passive"))
      (node (ref "C471") (pin "1") (pinfunction "1_1") (pintype "passive"))
      (node (ref "C477") (pin "1") (pinfunction "1_1") (pintype "passive"))
      (node (ref "C493") (pin "1") (pinfunction "1_1") (pintype "passive"))
      (node (ref "C701") (pin "1") (pinfunction "1_1") (pintype "passive"))
      (node (ref "J401") (pin "6") (pinfunction "6_6") (pintype "passive"))
      (node (ref "J404") (pin "3") (pinfunction "3_3") (pintype "passive"))
      (node (ref "J406") (pin "11") (pinfunction "11_11") (pintype "passive"))
      (node (ref "J701") (pin "4") (pinfunction "VCC_4") (pintype "bidirectional"))
      (node (ref "Q050") (pin "2") (pinfunction "S_2") (pintype "passive"))
      (node (ref "R051") (pin "1") (pinfunction "1_1") (pintype "passive"))
      (node (ref "R401") (pin "1") (pinfunction "1_1") (pintype "passive"))
      (node (ref "R401") (pin "2") (pinfunction "1_2") (pintype "passive"))
      (node (ref "R401") (pin "3") (pinfunction "1_3") (pintype "passive"))
      (node (ref "R401") (pin "4") (pinfunction "1_4") (pintype "passive"))
      (node (ref "S401") (pin "2") (pinfunction "2_2") (pintype "passive"))
      (node (ref "U1") (pin "10") (pinfunction "VDDA_10") (pintype "bidirectional"))
      (node (ref "U1") (pin "12") (pinfunction "VREF_12") (pintype "bidirectional"))
      (node (ref "U1") (pin "13") (pinfunction "VDD(DCDC)0_13") (pintype "bidirectional"))
      (node (ref "U1") (pin "19") (pinfunction "VBAT_19") (pintype "bidirectional"))
      (node (ref "U1") (pin "28") (pinfunction "VDD(3V3)0_28") (pintype "bidirectional"))
      (node (ref "U1") (pin "42") (pinfunction "VDD(DCDC)1_42") (pintype "bidirectional"))
      (node (ref "U1") (pin "54") (pinfunction "VDD(3V3)1_54") (pintype "bidirectional"))
      (node (ref "U1") (pin "71") (pinfunction "VDD(3V3)2_71") (pintype "bidirectional"))
      (node (ref "U1") (pin "77") (pinfunction "VDD(3V3)3_77") (pintype "bidirectional"))
      (node (ref "U1") (pin "93") (pinfunction "VDD(DCDC)2_93") (pintype "bidirectional"))
      (node (ref "U101") (pin "3") (pinfunction "VCC_3") (pintype "bidirectional"))
      (node (ref "U201") (pin "5") (pinfunction "VOUT_5") (pintype "bidirectional"))
      (node (ref "U402") (pin "1") (pinfunction "VCC_1") (pintype "bidirectional"))
    )
    (net (code "64") (name "unconnected-(J701-SHIELD-PadCD1)") (class "Default")
      (node (ref "J701") (pin "CD1") (pinfunction "SHIELD_CD1") (pintype "bidirectional"))
    )
    (net (code "65") (name "unconnected-(U1-#RSTOUT-Pad14)") (class "Default")
      (node (ref "U1") (pin "14") (pinfunction "#RSTOUT_14") (pintype "bidirectional"))
    )
    (net (code "66") (name "unconnected-(U1-#TRST-Pad4)") (class "Default")
      (node (ref "U1") (pin "4") (pinfunction "#TRST_4") (pintype "bidirectional"))
    )
    (net (code "67") (name "unconnected-(U1-P0[4]{slash}I2SRX_CLK{slash}RD2{slash}CAP2[0]-Pad90)") (class "Default")
      (node (ref "U1") (pin "90") (pinfunction "P0[4]/I2SRX_CLK/RD2/CAP2[0]_90") (pintype "bidirectional"))
    )
    (net (code "68") (name "unconnected-(U1-P0[5]{slash}I2SRX_WS{slash}TD2{slash}CAP2[1]-Pad89)") (class "Default")
      (node (ref "U1") (pin "89") (pinfunction "P0[5]/I2SRX_WS/TD2/CAP2[1]_89") (pintype "bidirectional"))
    )
    (net (code "69") (name "unconnected-(U1-P0[10]{slash}TXD2{slash}SDA2{slash}MAT3[0]-Pad48)") (class "Default")
      (node (ref "U1") (pin "48") (pinfunction "P0[10]/TXD2/SDA2/MAT3[0]_48") (pintype "bidirectional"))
    )
    (net (code "70") (name "unconnected-(U1-P0[11]{slash}RXD2{slash}SCL2{slash}MAT3[1]-Pad49)") (class "Default")
      (node (ref "U1") (pin "49") (pinfunction "P0[11]/RXD2/SCL2/MAT3[1]_49") (pintype "bidirectional"))
    )
    (net (code "71") (name "unconnected-(U1-P0[17]{slash}CTS1{slash}MISO0{slash}MISO-Pad61)") (class "Default")
      (node (ref "U1") (pin "61") (pinfunction "P0[17]/CTS1/MISO0/MISO_61") (pintype "bidirectional"))
    )
    (net (code "72") (name "unconnected-(U1-P0[18]{slash}DCD1{slash}MOSI0{slash}MOSI-Pad60)") (class "Default")
      (node (ref "U1") (pin "60") (pinfunction "P0[18]/DCD1/MOSI0/MOSI_60") (pintype "bidirectional"))
    )
    (net (code "73") (name "unconnected-(U1-P0[21]{slash}RI1{slash}MCIPWR{slash}RD1-Pad57)") (class "Default")
      (node (ref "U1") (pin "57") (pinfunction "P0[21]/RI1/MCIPWR/RD1_57") (pintype "bidirectional"))
    )
    (net (code "74") (name "unconnected-(U1-P1[4]{slash}ENET_TX_EN-Pad80)") (class "Default")
      (node (ref "U1") (pin "80") (pinfunction "P1[4]/ENET_TX_EN_80") (pintype "bidirectional"))
    )
    (net (code "75") (name "unconnected-(U1-P1[8]{slash}ENET_CRS-Pad81)") (class "Default")
      (node (ref "U1") (pin "81") (pinfunction "P1[8]/ENET_CRS_81") (pintype "bidirectional"))
    )
    (net (code "76") (name "unconnected-(U1-P1[9]{slash}ENET_RXD0-Pad100)") (class "Default")
      (node (ref "U1") (pin "100") (pinfunction "P1[9]/ENET_RXD0_100") (pintype "bidirectional"))
    )
    (net (code "77") (name "unconnected-(U1-P1[10]{slash}ENET_RXD1-Pad99)") (class "Default")
      (node (ref "U1") (pin "99") (pinfunction "P1[10]/ENET_RXD1_99") (pintype "bidirectional"))
    )
    (net (code "78") (name "unconnected-(U1-P1[14]{slash}ENET_RX_ER-Pad98)") (class "Default")
      (node (ref "U1") (pin "98") (pinfunction "P1[14]/ENET_RX_ER_98") (pintype "bidirectional"))
    )
    (net (code "79") (name "unconnected-(U1-P1[15]{slash}ENET_REF_CLK-Pad97)") (class "Default")
      (node (ref "U1") (pin "97") (pinfunction "P1[15]/ENET_REF_CLK_97") (pintype "bidirectional"))
    )
    (net (code "80") (name "unconnected-(U1-P1[16]{slash}ENET_MDC-Pad96)") (class "Default")
      (node (ref "U1") (pin "96") (pinfunction "P1[16]/ENET_MDC_96") (pintype "bidirectional"))
    )
    (net (code "81") (name "unconnected-(U1-P1[17]{slash}ENET_MDIO-Pad95)") (class "Default")
      (node (ref "U1") (pin "95") (pinfunction "P1[17]/ENET_MDIO_95") (pintype "bidirectional"))
    )
    (net (code "82") (name "unconnected-(U1-P1[19]{slash}CAP1[1]-Pad33)") (class "Default")
      (node (ref "U1") (pin "33") (pinfunction "P1[19]/CAP1[1]_33") (pintype "bidirectional"))
    )
    (net (code "83") (name "unconnected-(U1-P1[20]{slash}PWM1[2]{slash}SCK0-Pad34)") (class "Default")
      (node (ref "U1") (pin "34") (pinfunction "P1[20]/PWM1[2]/SCK0_34") (pintype "bidirectional"))
    )
    (net (code "84") (name "unconnected-(U1-P1[21]{slash}PWM1[2]{slash}SSEL0-Pad35)") (class "Default")
      (node (ref "U1") (pin "35") (pinfunction "P1[21]/PWM1[2]/SSEL0_35") (pintype "bidirectional"))
    )
    (net (code "85") (name "unconnected-(U1-P1[22]{slash}MAT1[0]-Pad36)") (class "Default")
      (node (ref "U1") (pin "36") (pinfunction "P1[22]/MAT1[0]_36") (pintype "bidirectional"))
    )
    (net (code "86") (name "unconnected-(U1-P1[23]{slash}PWM1[4]{slash}MISO0-Pad37)") (class "Default")
      (node (ref "U1") (pin "37") (pinfunction "P1[23]/PWM1[4]/MISO0_37") (pintype "bidirectional"))
    )
    (net (code "87") (name "unconnected-(U1-P1[24]{slash}PWM1[5]{slash}MOSI0-Pad38)") (class "Default")
      (node (ref "U1") (pin "38") (pinfunction "P1[24]/PWM1[5]/MOSI0_38") (pintype "bidirectional"))
    )
    (net (code "88") (name "unconnected-(U1-P1[25]{slash}MAT1[1]-Pad39)") (class "Default")
      (node (ref "U1") (pin "39") (pinfunction "P1[25]/MAT1[1]_39") (pintype "bidirectional"))
    )
    (net (code "89") (name "unconnected-(U1-P1[28]{slash}PCAP1[0]{slash}MAT0[0]-Pad44)") (class "Default")
      (node (ref "U1") (pin "44") (pinfunction "P1[28]/PCAP1[0]/MAT0[0]_44") (pintype "bidirectional"))
    )
    (net (code "90") (name "unconnected-(U1-P1[29]{slash}PCAP1[1]{slash}MAT0[1]-Pad45)") (class "Default")
      (node (ref "U1") (pin "45") (pinfunction "P1[29]/PCAP1[1]/MAT0[1]_45") (pintype "bidirectional"))
    )
    (net (code "91") (name "unconnected-(U1-P2[6]{slash}PCAP1[0]{slash}RI1{slash}TRACEPKT1-Pad67)") (class "Default")
      (node (ref "U1") (pin "67") (pinfunction "P2[6]/PCAP1[0]/RI1/TRACEPKT1_67") (pintype "bidirectional"))
    )
    (net (code "92") (name "unconnected-(U1-P2[7]{slash}RD2{slash}RTS1{slash}TRACEPKT2-Pad66)") (class "Default")
      (node (ref "U1") (pin "66") (pinfunction "P2[7]/RD2/RTS1/TRACEPKT2_66") (pintype "bidirectional"))
    )
    (net (code "93") (name "unconnected-(U1-P2[8]{slash}TD2{slash}TXD2{slash}TRACEPKT3-Pad65)") (class "Default")
      (node (ref "U1") (pin "65") (pinfunction "P2[8]/TD2/TXD2/TRACEPKT3_65") (pintype "bidirectional"))
    )
    (net (code "94") (name "unconnected-(U1-P3[25]{slash}MAT0[0]{slash}PWM1[2]-Pad27)") (class "Default")
      (node (ref "U1") (pin "27") (pinfunction "P3[25]/MAT0[0]/PWM1[2]_27") (pintype "bidirectional"))
    )
    (net (code "95") (name "unconnected-(U1-P3[26]{slash}MAT0[1]{slash}PWM1[3]-Pad26)") (class "Default")
      (node (ref "U1") (pin "26") (pinfunction "P3[26]/MAT0[1]/PWM1[3]_26") (pintype "bidirectional"))
    )
    (net (code "96") (name "unconnected-(U1-P4[28]{slash}MAT2[0]{slash}TXD3-Pad91)") (class "Default")
      (node (ref "U1") (pin "91") (pinfunction "P4[28]/MAT2[0]/TXD3_91") (pintype "bidirectional"))
    )
    (net (code "97") (name "unconnected-(U1-P4[29]{slash}MAT2[1]{slash}RXD3-Pad94)") (class "Default")
      (node (ref "U1") (pin "94") (pinfunction "P4[29]/MAT2[1]/RXD3_94") (pintype "bidirectional"))
    )
    (net (code "98") (name "unconnected-(U1-RTCK-Pad73)") (class "Default")
      (node (ref "U1") (pin "73") (pinfunction "RTCK_73") (pintype "bidirectional"))
    )
    (net (code "99") (name "unconnected-(U1-RTCX1-Pad16)") (class "Default")
      (node (ref "U1") (pin "16") (pinfunction "RTCX1_16") (pintype "bidirectional"))
    )
    (net (code "100") (name "unconnected-(U1-RTCX2-Pad18)") (class "Default")
      (node (ref "U1") (pin "18") (pinfunction "RTCX2_18") (pintype "bidirectional"))
    )
    (net (code "101") (name "unconnected-(U1-TCK-Pad5)") (class "Default")
      (node (ref "U1") (pin "5") (pinfunction "TCK_5") (pintype "bidirectional"))
    )
    (net (code "102") (name "unconnected-(U1-TD0-Pad1)") (class "Default")
      (node (ref "U1") (pin "1") (pinfunction "TD0_1") (pintype "bidirectional"))
    )
    (net (code "103") (name "unconnected-(U1-TDI-Pad2)") (class "Default")
      (node (ref "U1") (pin "2") (pinfunction "TDI_2") (pintype "bidirectional"))
    )
    (net (code "104") (name "unconnected-(U1-TMS-Pad3)") (class "Default")
      (node (ref "U1") (pin "3") (pinfunction "TMS_3") (pintype "bidirectional"))
    )
  )
)
